# TESTER_REMOTE_CONTROLLER_01.net
KiCad netlist of a schematic drawn in Altium Designer
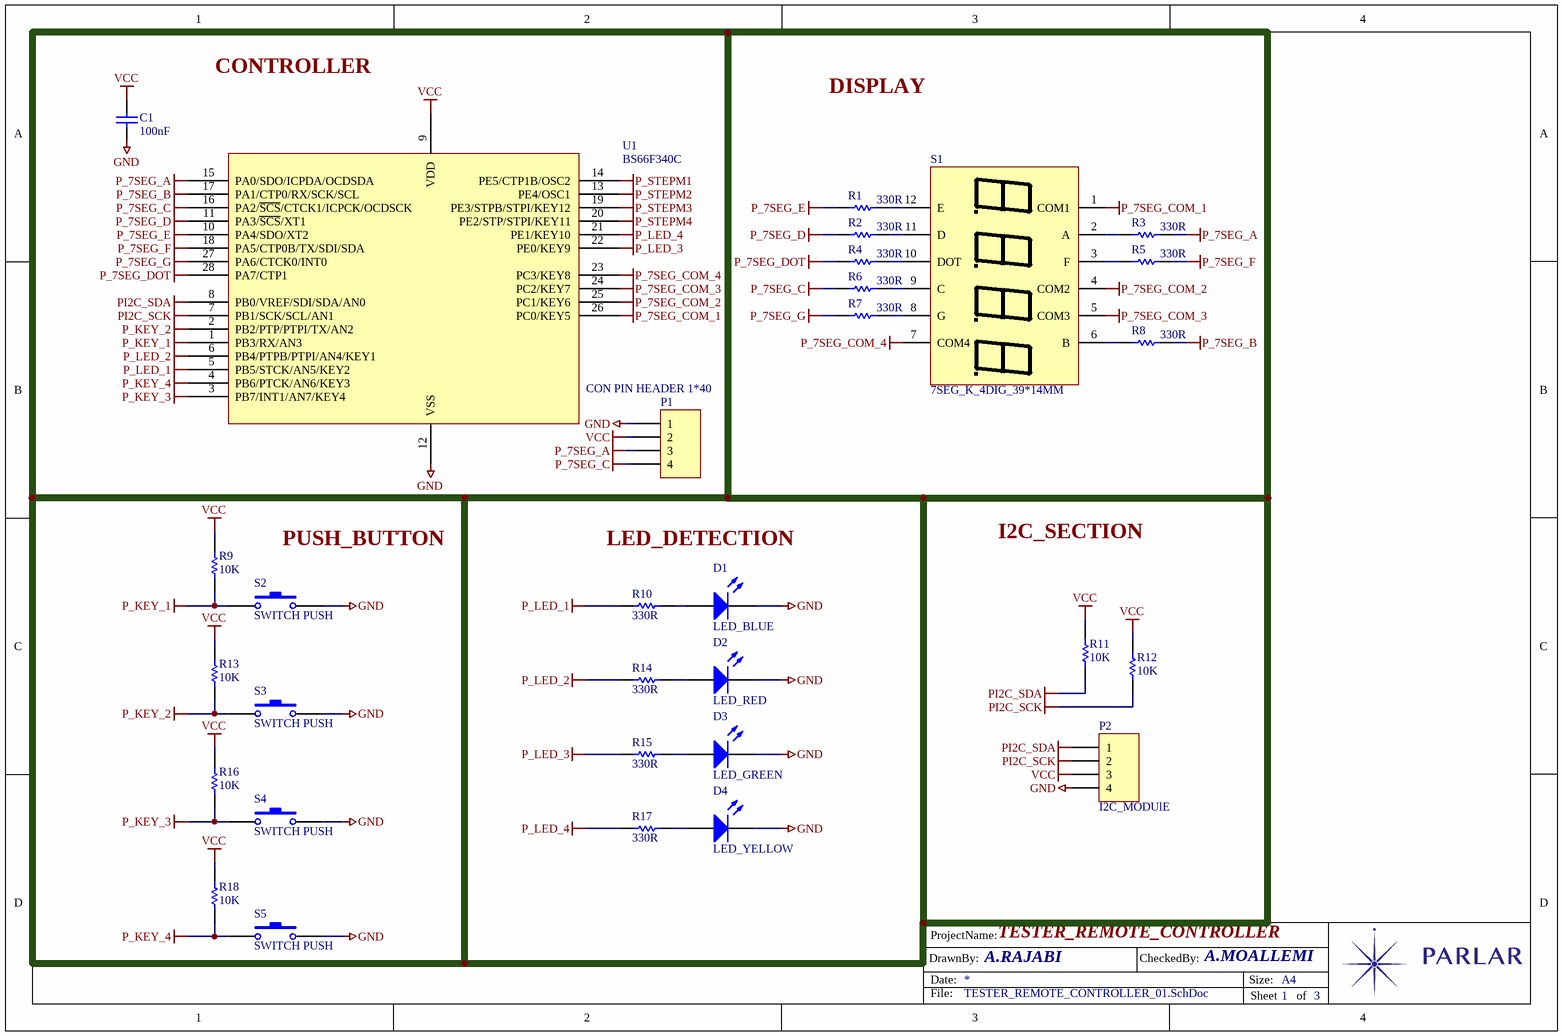
[diagram p0: TESTER_REMOTE_CONTROLLER_01.SchDoc]

(export (version "E")
  (design (tool "Eeschema 10.0.6"))
  (components
    (comp (ref "C1")
      (value "100nF")
      (footprint "SMD 0805")
      (description "Capacitor")
      (fields (field (name "PUBLISHER") "Altium Limited"))
      (libsource (lib "Parlarlib_24") (part "CAP"))
    )
    (comp (ref "D1")
      (value "LED_BLUE")
      (footprint "LED 5MM")
      (description "Typical INFRARED GaAs LED")
      (fields (field (name "PUBLISHER") "Altium Limited"))
      (libsource (lib "Parlarlib_24") (part "LED"))
    )
    (comp (ref "D2")
      (value "LED_RED")
      (footprint "LED 5MM")
      (description "Typical INFRARED GaAs LED")
      (fields (field (name "PUBLISHER") "Altium Limited"))
      (libsource (lib "Parlarlib_24") (part "LED"))
    )
    (comp (ref "D3")
      (value "LED_GREEN")
      (footprint "LED 5MM")
      (description "Typical INFRARED GaAs LED")
      (fields (field (name "PUBLISHER") "Altium Limited"))
      (libsource (lib "Parlarlib_24") (part "LED"))
    )
    (comp (ref "D4")
      (value "LED_YELLOW")
      (footprint "LED 5MM")
      (description "Typical INFRARED GaAs LED")
      (fields (field (name "PUBLISHER") "Altium Limited"))
      (libsource (lib "Parlarlib_24") (part "LED"))
    )
    (comp (ref "P1")
      (value "CON PIN HEADER 1*40")
      (footprint "CON HDR 2.54FM 4")
      (description "Header, 4-Pin")
      (fields (field (name "PUBLISHER") "Altium Limited"))
      (libsource (lib "Parlarlib_23") (part "CONNECTOR 4"))
    )
    (comp (ref "P2")
      (value "I2C_MODUlE")
      (footprint "CON HDR 2.54FM 4")
      (description "Header, 4-Pin")
      (fields (field (name "PUBLISHER") "Altium Limited"))
      (libsource (lib "Parlarlib_24") (part "CONNECTOR 4"))
    )
    (comp (ref "R1")
      (value "330R")
      (footprint "SMD 1206")
      (description "Resistor")
      (libsource (lib "Parlarlib_24") (part "RES"))
    )
    (comp (ref "R2")
      (value "330R")
      (footprint "SMD 1206")
      (description "Resistor")
      (libsource (lib "Parlarlib_24") (part "RES"))
    )
    (comp (ref "R3")
      (value "330R")
      (footprint "SMD 0805")
      (description "Resistor")
      (libsource (lib "Parlarlib_24") (part "RES"))
    )
    (comp (ref "R4")
      (value "330R")
      (footprint "SMD 1206")
      (description "Resistor")
      (libsource (lib "Parlarlib_24") (part "RES"))
    )
    (comp (ref "R5")
      (value "330R")
      (footprint "SMD 1206")
      (description "Resistor")
      (libsource (lib "Parlarlib_24") (part "RES"))
    )
    (comp (ref "R6")
      (value "330R")
      (footprint "SMD 0805")
      (description "Resistor")
      (libsource (lib "Parlarlib_24") (part "RES"))
    )
    (comp (ref "R7")
      (value "330R")
      (footprint "SMD 0805")
      (description "Resistor")
      (libsource (lib "Parlarlib_24") (part "RES"))
    )
    (comp (ref "R8")
      (value "330R")
      (footprint "SMD 0805")
      (description "Resistor")
      (libsource (lib "Parlarlib_24") (part "RES"))
    )
    (comp (ref "R9")
      (value "10K")
      (footprint "SMD 0805")
      (description "Resistor")
      (libsource (lib "Parlarlib_24") (part "RES"))
    )
    (comp (ref "R10")
      (value "330R")
      (footprint "SMD 0805")
      (description "Resistor")
      (libsource (lib "Parlarlib_24") (part "RES"))
    )
    (comp (ref "R11")
      (value "10K")
      (footprint "SMD 1206")
      (description "Resistor")
      (libsource (lib "Parlarlib_24") (part "RES"))
    )
    (comp (ref "R12")
      (value "10K")
      (footprint "SMD 0805")
      (description "Resistor")
      (libsource (lib "Parlarlib_24") (part "RES"))
    )
    (comp (ref "R13")
      (value "10K")
      (footprint "SMD 1206")
      (description "Resistor")
      (libsource (lib "Parlarlib_24") (part "RES"))
    )
    (comp (ref "R14")
      (value "330R")
      (footprint "SMD 0805")
      (description "Resistor")
      (libsource (lib "Parlarlib_24") (part "RES"))
    )
    (comp (ref "R15")
      (value "330R")
      (footprint "SMD 1206")
      (description "Resistor")
      (libsource (lib "Parlarlib_24") (part "RES"))
    )
    (comp (ref "R16")
      (value "10K")
      (footprint "SMD 1206")
      (description "Resistor")
      (libsource (lib "Parlarlib_24") (part "RES"))
    )
    (comp (ref "R17")
      (value "330R")
      (footprint "SMD 0805")
      (description "Resistor")
      (libsource (lib "Parlarlib_24") (part "RES"))
    )
    (comp (ref "R18")
      (value "10K")
      (footprint "SMD 0805")
      (description "Resistor")
      (libsource (lib "Parlarlib_24") (part "RES"))
    )
    (comp (ref "S1")
      (value "7SEG_K_4DIG_39*14MM")
      (footprint "SEVEN SEG K 12 PIN 4DIGIT RED X:30MM Y:14MM")
      (libsource (lib "Parlarlib_24") (part "7 SEG 4DIG"))
    )
    (comp (ref "S2")
      (value "SWITCH PUSH")
      (footprint "SW 6X6")
      (description "Switch")
      (fields (field (name "PUBLISHER") "Altium Limited"))
      (libsource (lib "Parlarlib_24") (part "SWITCH PUSH"))
    )
    (comp (ref "S3")
      (value "SWITCH PUSH")
      (footprint "SW 6X6")
      (description "Switch")
      (fields (field (name "PUBLISHER") "Altium Limited"))
      (libsource (lib "Parlarlib_24") (part "SWITCH PUSH"))
    )
    (comp (ref "S4")
      (value "SWITCH PUSH")
      (footprint "SW 6X6")
      (description "Switch")
      (fields (field (name "PUBLISHER") "Altium Limited"))
      (libsource (lib "Parlarlib_24") (part "SWITCH PUSH"))
    )
    (comp (ref "S5")
      (value "SWITCH PUSH")
      (footprint "SW 6X6")
      (description "Switch")
      (fields (field (name "PUBLISHER") "Altium Limited"))
      (libsource (lib "Parlarlib_24") (part "SWITCH PUSH"))
    )
    (comp (ref "U1")
      (value "BS66F340C")
      (footprint "SMD IC SSOP28-HOLTEK")
      (description "Enhanced Touch A/D Flash MCU, 28-Pin")
      (libsource (lib "Parlarlib_23") (part "IC BS66F340C"))
    )
  )
  (nets
    (net (code "6") (name "GND") (class "Default")
      (node (ref "C1") (pin "2") (pinfunction "2_2") (pintype "passive"))
      (node (ref "D1") (pin "2") (pinfunction "2_2") (pintype "passive"))
      (node (ref "D2") (pin "2") (pinfunction "2_2") (pintype "passive"))
      (node (ref "D3") (pin "2") (pinfunction "2_2") (pintype "passive"))
      (node (ref "D4") (pin "2") (pinfunction "2_2") (pintype "passive"))
      (node (ref "P1") (pin "1") (pinfunction "1_1") (pintype "passive"))
      (node (ref "P2") (pin "4") (pinfunction "4_4") (pintype "passive"))
      (node (ref "S2") (pin "2") (pinfunction "2_2") (pintype "passive"))
      (node (ref "S3") (pin "2") (pinfunction "2_2") (pintype "passive"))
      (node (ref "S4") (pin "2") (pinfunction "2_2") (pintype "passive"))
      (node (ref "S5") (pin "2") (pinfunction "2_2") (pintype "passive"))
      (node (ref "U1") (pin "12") (pinfunction "VSS_12") (pintype "passive"))
    )
    (net (code "7") (name "Net-(D1-Pad1)") (class "Default")
      (node (ref "D1") (pin "1") (pinfunction "1_1") (pintype "passive"))
      (node (ref "R10") (pin "2") (pinfunction "2_2") (pintype "passive"))
    )
    (net (code "8") (name "Net-(D2-Pad1)") (class "Default")
      (node (ref "D2") (pin "1") (pinfunction "1_1") (pintype "passive"))
      (node (ref "R14") (pin "2") (pinfunction "2_2") (pintype "passive"))
    )
    (net (code "9") (name "Net-(D3-Pad1)") (class "Default")
      (node (ref "D3") (pin "1") (pinfunction "1_1") (pintype "passive"))
      (node (ref "R15") (pin "2") (pinfunction "2_2") (pintype "passive"))
    )
    (net (code "10") (name "Net-(D4-Pad1)") (class "Default")
      (node (ref "D4") (pin "1") (pinfunction "1_1") (pintype "passive"))
      (node (ref "R17") (pin "2") (pinfunction "2_2") (pintype "passive"))
    )
    (net (code "11") (name "Net-(S1-A)") (class "Default")
      (node (ref "R3") (pin "1") (pinfunction "1_1") (pintype "passive"))
      (node (ref "S1") (pin "2") (pinfunction "A_2") (pintype "passive"))
    )
    (net (code "12") (name "Net-(S1-B)") (class "Default")
      (node (ref "R8") (pin "1") (pinfunction "1_1") (pintype "passive"))
      (node (ref "S1") (pin "6") (pinfunction "B_6") (pintype "passive"))
    )
    (net (code "13") (name "Net-(S1-C)") (class "Default")
      (node (ref "R6") (pin "2") (pinfunction "2_2") (pintype "passive"))
      (node (ref "S1") (pin "9") (pinfunction "C_9") (pintype "passive"))
    )
    (net (code "14") (name "Net-(S1-D)") (class "Default")
      (node (ref "R2") (pin "2") (pinfunction "2_2") (pintype "passive"))
      (node (ref "S1") (pin "11") (pinfunction "D_11") (pintype "passive"))
    )
    (net (code "15") (name "Net-(S1-DOT)") (class "Default")
      (node (ref "R4") (pin "2") (pinfunction "2_2") (pintype "passive"))
      (node (ref "S1") (pin "10") (pinfunction "DOT_10") (pintype "passive"))
    )
    (net (code "16") (name "Net-(S1-E)") (class "Default")
      (node (ref "R1") (pin "2") (pinfunction "2_2") (pintype "passive"))
      (node (ref "S1") (pin "12") (pinfunction "E_12") (pintype "passive"))
    )
    (net (code "17") (name "Net-(S1-F)") (class "Default")
      (node (ref "R5") (pin "1") (pinfunction "1_1") (pintype "passive"))
      (node (ref "S1") (pin "3") (pinfunction "F_3") (pintype "passive"))
    )
    (net (code "18") (name "Net-(S1-G)") (class "Default")
      (node (ref "R7") (pin "2") (pinfunction "2_2") (pintype "passive"))
      (node (ref "S1") (pin "8") (pinfunction "G_8") (pintype "passive"))
    )
    (net (code "19") (name "PI2C_SCK") (class "Default")
      (node (ref "P2") (pin "2") (pinfunction "2_2") (pintype "passive"))
      (node (ref "R12") (pin "1") (pinfunction "1_1") (pintype "passive"))
      (node (ref "U1") (pin "7") (pinfunction "PB1/SCK/SCL/AN1_7") (pintype "passive"))
    )
    (net (code "20") (name "PI2C_SDA") (class "Default")
      (node (ref "P2") (pin "1") (pinfunction "1_1") (pintype "passive"))
      (node (ref "R11") (pin "1") (pinfunction "1_1") (pintype "passive"))
      (node (ref "U1") (pin "8") (pinfunction "PB0/VREF/SDI/SDA/AN0_8") (pintype "passive"))
    )
    (net (code "21") (name "P_7SEG_A") (class "Default")
      (node (ref "P1") (pin "3") (pinfunction "3_3") (pintype "passive"))
      (node (ref "R3") (pin "2") (pinfunction "2_2") (pintype "passive"))
      (node (ref "U1") (pin "15") (pinfunction "PA0/SDO/ICPDA/OCDSDA_15") (pintype "passive"))
    )
    (net (code "22") (name "P_7SEG_B") (class "Default")
      (node (ref "R8") (pin "2") (pinfunction "2_2") (pintype "passive"))
      (node (ref "U1") (pin "17") (pinfunction "PA1/CTP0/RX/SCK/SCL_17") (pintype "passive"))
    )
    (net (code "23") (name "P_7SEG_C") (class "Default")
      (node (ref "P1") (pin "4") (pinfunction "4_4") (pintype "passive"))
      (node (ref "R6") (pin "1") (pinfunction "1_1") (pintype "passive"))
      (node (ref "U1") (pin "16") (pinfunction "PA2/~{SCS}/CTCK1/ICPCK/OCDSCK_16") (pintype "passive"))
    )
    (net (code "24") (name "P_7SEG_COM_1") (class "Default")
      (node (ref "S1") (pin "1") (pinfunction "COM1_1") (pintype "passive"))
      (node (ref "U1") (pin "26") (pinfunction "PC0/KEY5_26") (pintype "passive"))
    )
    (net (code "25") (name "P_7SEG_COM_2") (class "Default")
      (node (ref "S1") (pin "4") (pinfunction "COM2_4") (pintype "passive"))
      (node (ref "U1") (pin "25") (pinfunction "PC1/KEY6_25") (pintype "passive"))
    )
    (net (code "26") (name "P_7SEG_COM_3") (class "Default")
      (node (ref "S1") (pin "5") (pinfunction "COM3_5") (pintype "passive"))
      (node (ref "U1") (pin "24") (pinfunction "PC2/KEY7_24") (pintype "passive"))
    )
    (net (code "27") (name "P_7SEG_COM_4") (class "Default")
      (node (ref "S1") (pin "7") (pinfunction "COM4_7") (pintype "passive"))
      (node (ref "U1") (pin "23") (pinfunction "PC3/KEY8_23") (pintype "passive"))
    )
    (net (code "28") (name "P_7SEG_D") (class "Default")
      (node (ref "R2") (pin "1") (pinfunction "1_1") (pintype "passive"))
      (node (ref "U1") (pin "11") (pinfunction "PA3/~{SCS}/XT1_11") (pintype "passive"))
    )
    (net (code "29") (name "P_7SEG_DOT") (class "Default")
      (node (ref "R4") (pin "1") (pinfunction "1_1") (pintype "passive"))
      (node (ref "U1") (pin "28") (pinfunction "PA7/CTP1_28") (pintype "passive"))
    )
    (net (code "30") (name "P_7SEG_E") (class "Default")
      (node (ref "R1") (pin "1") (pinfunction "1_1") (pintype "passive"))
      (node (ref "U1") (pin "10") (pinfunction "PA4/SDO/XT2_10") (pintype "passive"))
    )
    (net (code "31") (name "P_7SEG_F") (class "Default")
      (node (ref "R5") (pin "2") (pinfunction "2_2") (pintype "passive"))
      (node (ref "U1") (pin "18") (pinfunction "PA5/CTP0B/TX/SDI/SDA_18") (pintype "passive"))
    )
    (net (code "32") (name "P_7SEG_G") (class "Default")
      (node (ref "R7") (pin "1") (pinfunction "1_1") (pintype "passive"))
      (node (ref "U1") (pin "27") (pinfunction "PA6/CTCK0/INT0_27") (pintype "passive"))
    )
    (net (code "33") (name "P_KEY_1") (class "Default")
      (node (ref "R9") (pin "1") (pinfunction "1_1") (pintype "passive"))
      (node (ref "S2") (pin "1") (pinfunction "1_1") (pintype "passive"))
      (node (ref "U1") (pin "1") (pinfunction "PB3/RX/AN3_1") (pintype "passive"))
    )
    (net (code "34") (name "P_KEY_2") (class "Default")
      (node (ref "R13") (pin "1") (pinfunction "1_1") (pintype "passive"))
      (node (ref "S3") (pin "1") (pinfunction "1_1") (pintype "passive"))
      (node (ref "U1") (pin "2") (pinfunction "PB2/PTP/PTPI/TX/AN2_2") (pintype "passive"))
    )
    (net (code "35") (name "P_KEY_3") (class "Default")
      (node (ref "R16") (pin "1") (pinfunction "1_1") (pintype "passive"))
      (node (ref "S4") (pin "1") (pinfunction "1_1") (pintype "passive"))
      (node (ref "U1") (pin "3") (pinfunction "PB7/INT1/AN7/KEY4_3") (pintype "passive"))
    )
    (net (code "36") (name "P_KEY_4") (class "Default")
      (node (ref "R18") (pin "1") (pinfunction "1_1") (pintype "passive"))
      (node (ref "S5") (pin "1") (pinfunction "1_1") (pintype "passive"))
      (node (ref "U1") (pin "4") (pinfunction "PB6/PTCK/AN6/KEY3_4") (pintype "passive"))
    )
    (net (code "37") (name "P_LED_1") (class "Default")
      (node (ref "R10") (pin "1") (pinfunction "1_1") (pintype "passive"))
      (node (ref "U1") (pin "5") (pinfunction "PB5/STCK/AN5/KEY2_5") (pintype "passive"))
    )
    (net (code "38") (name "P_LED_2") (class "Default")
      (node (ref "R14") (pin "1") (pinfunction "1_1") (pintype "passive"))
      (node (ref "U1") (pin "6") (pinfunction "PB4/PTPB/PTPI/AN4/KEY1_6") (pintype "passive"))
    )
    (net (code "39") (name "P_LED_3") (class "Default")
      (node (ref "R15") (pin "1") (pinfunction "1_1") (pintype "passive"))
      (node (ref "U1") (pin "22") (pinfunction "PE0/KEY9_22") (pintype "passive"))
    )
    (net (code "40") (name "P_LED_4") (class "Default")
      (node (ref "R17") (pin "1") (pinfunction "1_1") (pintype "passive"))
      (node (ref "U1") (pin "21") (pinfunction "PE1/KEY10_21") (pintype "passive"))
    )
    (net (code "41") (name "P_STEPM1") (class "Default")
      (node (ref "U1") (pin "14") (pinfunction "PE5/CTP1B/OSC2_14") (pintype "passive"))
    )
    (net (code "42") (name "P_STEPM2") (class "Default")
      (node (ref "U1") (pin "13") (pinfunction "PE4/OSC1_13") (pintype "passive"))
    )
    (net (code "43") (name "P_STEPM3") (class "Default")
      (node (ref "U1") (pin "19") (pinfunction "PE3/STPB/STPI/KEY12_19") (pintype "passive"))
    )
    (net (code "44") (name "P_STEPM4") (class "Default")
      (node (ref "U1") (pin "20") (pinfunction "PE2/STP/STPI/KEY11_20") (pintype "passive"))
    )
    (net (code "45") (name "VCC") (class "Default")
      (node (ref "C1") (pin "1") (pinfunction "1_1") (pintype "passive"))
      (node (ref "P1") (pin "2") (pinfunction "2_2") (pintype "passive"))
      (node (ref "P2") (pin "3") (pinfunction "3_3") (pintype "passive"))
      (node (ref "R11") (pin "2") (pinfunction "2_2") (pintype "passive"))
      (node (ref "R12") (pin "2") (pinfunction "2_2") (pintype "passive"))
      (node (ref "R13") (pin "2") (pinfunction "2_2") (pintype "passive"))
      (node (ref "R16") (pin "2") (pinfunction "2_2") (pintype "passive"))
      (node (ref "R18") (pin "2") (pinfunction "2_2") (pintype "passive"))
      (node (ref "R9") (pin "2") (pinfunction "2_2") (pintype "passive"))
      (node (ref "U1") (pin "9") (pinfunction "VDD_9") (pintype "passive"))
    )
  )
)
